# Neonatal_Circuit.net
KiCad netlist of a schematic drawn in EAGLE
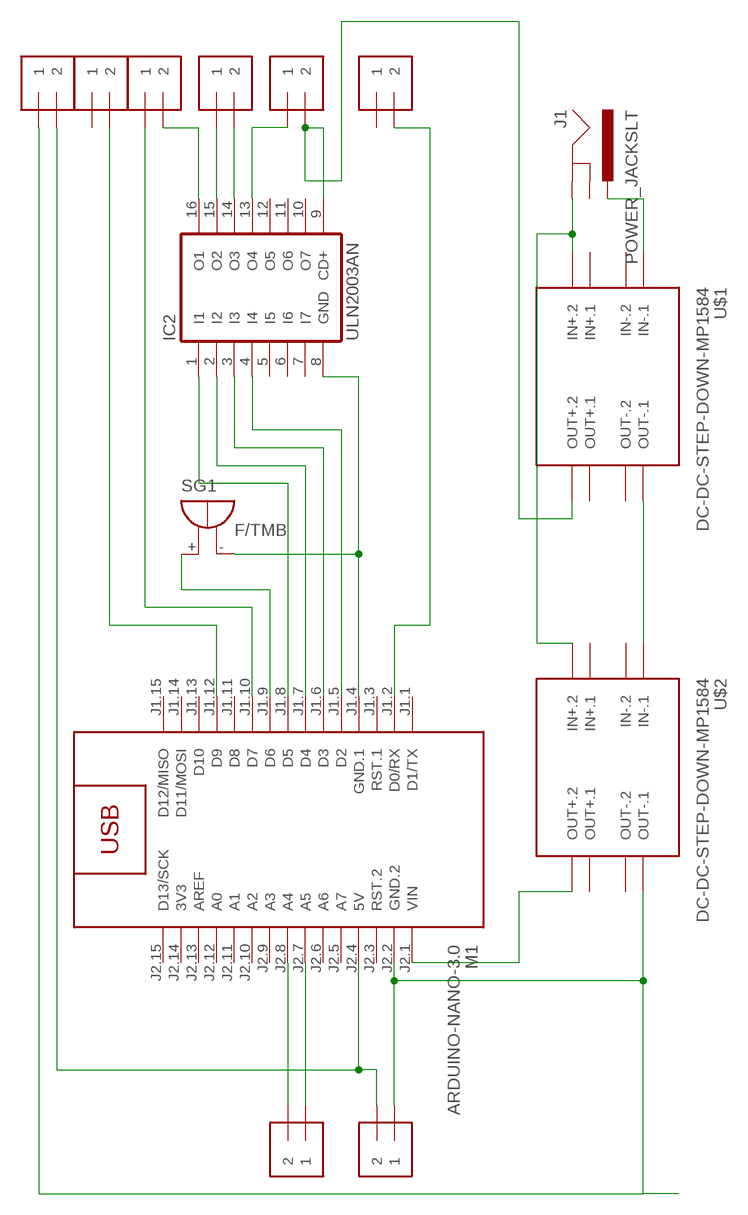
[diagram p0: schematic, sheet 1]

(export (version "E")
  (design (tool "Eeschema 10.0.6"))
  (components
    (comp (ref "IC2")
      (value "ULN2003AN")
      (footprint "eagle-import:DIL16")
      (libsource (lib "eagle-import") (part "ULN2003AN"))
    )
    (comp (ref "J1")
      (value "POWER_JACKSLT")
      (footprint "eagle-import:POWER_JACK_SLOT")
      (libsource (lib "eagle-import") (part "POWER_JACKSLT"))
    )
    (comp (ref "J2")
      (value "1X2-3.5MM")
      (footprint "eagle-import:1X2-3.5MM")
      (libsource (lib "eagle-import") (part "1X2-3.5MM"))
    )
    (comp (ref "J3")
      (value "1X2-3.5MM")
      (footprint "eagle-import:1X2-3.5MM")
      (libsource (lib "eagle-import") (part "1X2-3.5MM"))
    )
    (comp (ref "J4")
      (value "1X2-3.5MM")
      (footprint "eagle-import:1X2-3.5MM")
      (libsource (lib "eagle-import") (part "1X2-3.5MM"))
    )
    (comp (ref "J5")
      (value "1X2-3.5MM")
      (footprint "eagle-import:1X2-3.5MM")
      (libsource (lib "eagle-import") (part "1X2-3.5MM"))
    )
    (comp (ref "J6")
      (value "1X2-3.5MM")
      (footprint "eagle-import:1X2-3.5MM")
      (libsource (lib "eagle-import") (part "1X2-3.5MM"))
    )
    (comp (ref "J7")
      (value "1X2-3.5MM")
      (footprint "eagle-import:1X2-3.5MM")
      (libsource (lib "eagle-import") (part "1X2-3.5MM"))
    )
    (comp (ref "J8")
      (value "1X2-3.5MM")
      (footprint "eagle-import:1X2-3.5MM")
      (libsource (lib "eagle-import") (part "1X2-3.5MM"))
    )
    (comp (ref "J9")
      (value "1X2-3.5MM")
      (footprint "eagle-import:1X2-3.5MM")
      (libsource (lib "eagle-import") (part "1X2-3.5MM"))
    )
    (comp (ref "M1")
      (value "ARDUINO-NANO-3.0")
      (footprint "eagle-import:ARDUINO-NANO-3.0")
      (libsource (lib "eagle-import") (part "ARDUINO-NANO-3.0"))
    )
    (comp (ref "SG1")
      (value "F/TMB")
      (footprint "eagle-import:F_TMB")
      (libsource (lib "eagle-import") (part "F/TMB"))
    )
    (comp (ref "U$1")
      (value "DC-DC-STEP-DOWN-MP1584")
      (footprint "eagle-import:DC-DC-STEP-DOWN-MP1584")
      (libsource (lib "eagle-import") (part "DC-DC-STEP-DOWN-MP1584"))
    )
    (comp (ref "U$2")
      (value "DC-DC-STEP-DOWN-MP1584")
      (footprint "eagle-import:DC-DC-STEP-DOWN-MP1584")
      (libsource (lib "eagle-import") (part "DC-DC-STEP-DOWN-MP1584"))
    )
  )
  (nets
    (net (code "1") (name "/3V3") (class "Default")
      (node (ref "M1") (pin "J2.14") (pinfunction "3V3_J2.14") (pintype "power_in"))
    )
    (net (code "2") (name "Net-(IC2-CD+)") (class "Default")
      (node (ref "IC2") (pin "9") (pinfunction "CD+_9") (pintype "passive"))
      (node (ref "J4") (pin "2") (pinfunction "2_2") (pintype "passive"))
      (node (ref "U$1") (pin "OUT+.2") (pinfunction "OUT+.2_OUT+.2") (pintype "bidirectional"))
    )
    (net (code "3") (name "Net-(IC2-GND)") (class "Default")
      (node (ref "IC2") (pin "8") (pinfunction "GND_8") (pintype "power_in"))
      (node (ref "M1") (pin "J1.4") (pinfunction "GND.1_J1.4") (pintype "power_in"))
      (node (ref "SG1") (pin "-") (pinfunction "-_-") (pintype "passive"))
    )
    (net (code "4") (name "Net-(IC2-I1)") (class "Default")
      (node (ref "IC2") (pin "1") (pinfunction "I1_1") (pintype "input"))
      (node (ref "M1") (pin "J1.8") (pinfunction "D5_J1.8") (pintype "bidirectional"))
    )
    (net (code "5") (name "Net-(IC2-I2)") (class "Default")
      (node (ref "IC2") (pin "2") (pinfunction "I2_2") (pintype "input"))
      (node (ref "M1") (pin "J1.7") (pinfunction "D4_J1.7") (pintype "bidirectional"))
    )
    (net (code "6") (name "Net-(IC2-I3)") (class "Default")
      (node (ref "IC2") (pin "3") (pinfunction "I3_3") (pintype "input"))
      (node (ref "M1") (pin "J1.6") (pinfunction "D3_J1.6") (pintype "bidirectional"))
    )
    (net (code "7") (name "Net-(IC2-I4)") (class "Default")
      (node (ref "IC2") (pin "4") (pinfunction "I4_4") (pintype "input"))
      (node (ref "M1") (pin "J1.5") (pinfunction "D2_J1.5") (pintype "bidirectional"))
    )
    (net (code "8") (name "Net-(IC2-O1)") (class "Default")
      (node (ref "IC2") (pin "16") (pinfunction "O1_16") (pintype "open_collector"))
      (node (ref "J6") (pin "2") (pinfunction "2_2") (pintype "passive"))
    )
    (net (code "9") (name "Net-(IC2-O2)") (class "Default")
      (node (ref "IC2") (pin "15") (pinfunction "O2_15") (pintype "open_collector"))
      (node (ref "J5") (pin "1") (pinfunction "1_1") (pintype "passive"))
    )
    (net (code "10") (name "Net-(IC2-O3)") (class "Default")
      (node (ref "IC2") (pin "14") (pinfunction "O3_14") (pintype "open_collector"))
      (node (ref "J5") (pin "2") (pinfunction "2_2") (pintype "passive"))
    )
    (net (code "11") (name "Net-(IC2-O4)") (class "Default")
      (node (ref "IC2") (pin "13") (pinfunction "O4_13") (pintype "open_collector"))
      (node (ref "J4") (pin "1") (pinfunction "1_1") (pintype "passive"))
    )
    (net (code "12") (name "Net-(J1-GND)") (class "Default")
      (node (ref "J1") (pin "GND@2") (pinfunction "GND_GND@2") (pintype "bidirectional"))
      (node (ref "U$1") (pin "IN+.2") (pinfunction "IN+.2_IN+.2") (pintype "bidirectional"))
      (node (ref "U$2") (pin "IN+.2") (pinfunction "IN+.2_IN+.2") (pintype "bidirectional"))
    )
    (net (code "13") (name "Net-(J1-PadPWR)") (class "Default")
      (node (ref "J1") (pin "PWR") (pinfunction "PWR_PWR") (pintype "bidirectional"))
      (node (ref "U$1") (pin "IN-.1") (pinfunction "IN-.1_IN-.1") (pintype "bidirectional"))
    )
    (net (code "14") (name "Net-(M1-5V)") (class "Default")
      (node (ref "J7") (pin "2") (pinfunction "2_2") (pintype "passive"))
      (node (ref "J8") (pin "2") (pinfunction "2_2") (pintype "passive"))
      (node (ref "M1") (pin "J2.4") (pinfunction "5V_J2.4") (pintype "power_in"))
    )
    (net (code "15") (name "Net-(M1-A4)") (class "Default")
      (node (ref "J9") (pin "2") (pinfunction "2_2") (pintype "passive"))
      (node (ref "M1") (pin "J2.8") (pinfunction "A4_J2.8") (pintype "bidirectional"))
    )
    (net (code "16") (name "Net-(M1-A5)") (class "Default")
      (node (ref "J9") (pin "1") (pinfunction "1_1") (pintype "passive"))
      (node (ref "M1") (pin "J2.7") (pinfunction "A5_J2.7") (pintype "bidirectional"))
    )
    (net (code "17") (name "Net-(M1-D0{slash}RX)") (class "Default")
      (node (ref "J3") (pin "2") (pinfunction "2_2") (pintype "passive"))
      (node (ref "M1") (pin "J1.2") (pinfunction "D0/RX_J1.2") (pintype "bidirectional"))
    )
    (net (code "18") (name "Net-(M1-D6)") (class "Default")
      (node (ref "M1") (pin "J1.9") (pinfunction "D6_J1.9") (pintype "bidirectional"))
      (node (ref "SG1") (pin "+") (pinfunction "+_+") (pintype "passive"))
    )
    (net (code "19") (name "Net-(M1-D7)") (class "Default")
      (node (ref "J6") (pin "1") (pinfunction "1_1") (pintype "passive"))
      (node (ref "M1") (pin "J1.10") (pinfunction "D7_J1.10") (pintype "bidirectional"))
    )
    (net (code "20") (name "Net-(M1-D9)") (class "Default")
      (node (ref "J2") (pin "2") (pinfunction "2_2") (pintype "passive"))
      (node (ref "M1") (pin "J1.12") (pinfunction "D9_J1.12") (pintype "bidirectional"))
    )
    (net (code "21") (name "Net-(M1-GND.2)") (class "Default")
      (node (ref "J7") (pin "1") (pinfunction "1_1") (pintype "passive"))
      (node (ref "J8") (pin "1") (pinfunction "1_1") (pintype "passive"))
      (node (ref "M1") (pin "J2.2") (pinfunction "GND.2_J2.2") (pintype "power_in"))
      (node (ref "U$2") (pin "OUT-.1") (pinfunction "OUT-.1_OUT-.1") (pintype "bidirectional"))
    )
    (net (code "22") (name "Net-(M1-VIN)") (class "Default")
      (node (ref "M1") (pin "J2.1") (pinfunction "VIN_J2.1") (pintype "power_in"))
      (node (ref "U$2") (pin "OUT+.2") (pinfunction "OUT+.2_OUT+.2") (pintype "bidirectional"))
    )
    (net (code "23") (name "Net-(U$1-PadOUT-.1)") (class "Default")
      (node (ref "U$1") (pin "OUT-.1") (pinfunction "OUT-.1_OUT-.1") (pintype "bidirectional"))
      (node (ref "U$2") (pin "IN-.1") (pinfunction "IN-.1_IN-.1") (pintype "bidirectional"))
    )
    (net (code "24") (name "unconnected-(IC2-I5-Pad5)") (class "Default")
      (node (ref "IC2") (pin "5") (pinfunction "I5_5") (pintype "input"))
    )
    (net (code "25") (name "unconnected-(IC2-I6-Pad6)") (class "Default")
      (node (ref "IC2") (pin "6") (pinfunction "I6_6") (pintype "input"))
    )
    (net (code "26") (name "unconnected-(IC2-I7-Pad7)") (class "Default")
      (node (ref "IC2") (pin "7") (pinfunction "I7_7") (pintype "input"))
    )
    (net (code "27") (name "unconnected-(IC2-O5-Pad12)") (class "Default")
      (node (ref "IC2") (pin "12") (pinfunction "O5_12") (pintype "open_collector"))
    )
    (net (code "28") (name "unconnected-(IC2-O6-Pad11)") (class "Default")
      (node (ref "IC2") (pin "11") (pinfunction "O6_11") (pintype "open_collector"))
    )
    (net (code "29") (name "unconnected-(IC2-O7-Pad10)") (class "Default")
      (node (ref "IC2") (pin "10") (pinfunction "O7_10") (pintype "open_collector"))
    )
    (net (code "30") (name "unconnected-(J1-GNDBREAK-PadGND@1)") (class "Default")
      (node (ref "J1") (pin "GND@1") (pinfunction "GNDBREAK_GND@1") (pintype "bidirectional"))
    )
    (net (code "31") (name "unconnected-(J2-Pad1)") (class "Default")
      (node (ref "J2") (pin "1") (pinfunction "1_1") (pintype "passive"))
    )
    (net (code "32") (name "unconnected-(J3-Pad1)") (class "Default")
      (node (ref "J3") (pin "1") (pinfunction "1_1") (pintype "passive"))
    )
    (net (code "33") (name "unconnected-(M1-A0-PadJ2.12)") (class "Default")
      (node (ref "M1") (pin "J2.12") (pinfunction "A0_J2.12") (pintype "bidirectional"))
    )
    (net (code "34") (name "unconnected-(M1-A1-PadJ2.11)") (class "Default")
      (node (ref "M1") (pin "J2.11") (pinfunction "A1_J2.11") (pintype "bidirectional"))
    )
    (net (code "35") (name "unconnected-(M1-A2-PadJ2.10)") (class "Default")
      (node (ref "M1") (pin "J2.10") (pinfunction "A2_J2.10") (pintype "bidirectional"))
    )
    (net (code "36") (name "unconnected-(M1-A3-PadJ2.9)") (class "Default")
      (node (ref "M1") (pin "J2.9") (pinfunction "A3_J2.9") (pintype "bidirectional"))
    )
    (net (code "37") (name "unconnected-(M1-A6-PadJ2.6)") (class "Default")
      (node (ref "M1") (pin "J2.6") (pinfunction "A6_J2.6") (pintype "bidirectional"))
    )
    (net (code "38") (name "unconnected-(M1-A7-PadJ2.5)") (class "Default")
      (node (ref "M1") (pin "J2.5") (pinfunction "A7_J2.5") (pintype "bidirectional"))
    )
    (net (code "39") (name "unconnected-(M1-AREF-PadJ2.13)") (class "Default")
      (node (ref "M1") (pin "J2.13") (pinfunction "AREF_J2.13") (pintype "bidirectional"))
    )
    (net (code "40") (name "unconnected-(M1-D1{slash}TX-PadJ1.1)") (class "Default")
      (node (ref "M1") (pin "J1.1") (pinfunction "D1/TX_J1.1") (pintype "bidirectional"))
    )
    (net (code "41") (name "unconnected-(M1-D8-PadJ1.11)") (class "Default")
      (node (ref "M1") (pin "J1.11") (pinfunction "D8_J1.11") (pintype "bidirectional"))
    )
    (net (code "42") (name "unconnected-(M1-D10-PadJ1.13)") (class "Default")
      (node (ref "M1") (pin "J1.13") (pinfunction "D10_J1.13") (pintype "bidirectional"))
    )
    (net (code "43") (name "unconnected-(M1-D11{slash}MOSI-PadJ1.14)") (class "Default")
      (node (ref "M1") (pin "J1.14") (pinfunction "D11/MOSI_J1.14") (pintype "bidirectional"))
    )
    (net (code "44") (name "unconnected-(M1-D12{slash}MISO-PadJ1.15)") (class "Default")
      (node (ref "M1") (pin "J1.15") (pinfunction "D12/MISO_J1.15") (pintype "bidirectional"))
    )
    (net (code "45") (name "unconnected-(M1-D13{slash}SCK-PadJ2.15)") (class "Default")
      (node (ref "M1") (pin "J2.15") (pinfunction "D13/SCK_J2.15") (pintype "bidirectional"))
    )
    (net (code "46") (name "unconnected-(M1-RST.1-PadJ1.3)") (class "Default")
      (node (ref "M1") (pin "J1.3") (pinfunction "RST.1_J1.3") (pintype "bidirectional"))
    )
    (net (code "47") (name "unconnected-(M1-RST.2-PadJ2.3)") (class "Default")
      (node (ref "M1") (pin "J2.3") (pinfunction "RST.2_J2.3") (pintype "bidirectional"))
    )
    (net (code "48") (name "unconnected-(U$1-PadIN+.1)") (class "Default")
      (node (ref "U$1") (pin "IN+.1") (pinfunction "IN+.1_IN+.1") (pintype "bidirectional"))
    )
    (net (code "49") (name "unconnected-(U$1-PadIN-.2)") (class "Default")
      (node (ref "U$1") (pin "IN-.2") (pinfunction "IN-.2_IN-.2") (pintype "bidirectional"))
    )
    (net (code "50") (name "unconnected-(U$1-PadOUT+.1)") (class "Default")
      (node (ref "U$1") (pin "OUT+.1") (pinfunction "OUT+.1_OUT+.1") (pintype "bidirectional"))
    )
    (net (code "51") (name "unconnected-(U$1-PadOUT-.2)") (class "Default")
      (node (ref "U$1") (pin "OUT-.2") (pinfunction "OUT-.2_OUT-.2") (pintype "bidirectional"))
    )
    (net (code "52") (name "unconnected-(U$2-PadIN+.1)") (class "Default")
      (node (ref "U$2") (pin "IN+.1") (pinfunction "IN+.1_IN+.1") (pintype "bidirectional"))
    )
    (net (code "53") (name "unconnected-(U$2-PadIN-.2)") (class "Default")
      (node (ref "U$2") (pin "IN-.2") (pinfunction "IN-.2_IN-.2") (pintype "bidirectional"))
    )
    (net (code "54") (name "unconnected-(U$2-PadOUT+.1)") (class "Default")
      (node (ref "U$2") (pin "OUT+.1") (pinfunction "OUT+.1_OUT+.1") (pintype "bidirectional"))
    )
    (net (code "55") (name "unconnected-(U$2-PadOUT-.2)") (class "Default")
      (node (ref "U$2") (pin "OUT-.2") (pinfunction "OUT-.2_OUT-.2") (pintype "bidirectional"))
    )
  )
)
